# 3_-STM32F103_Debugger.net
KiCad netlist of a schematic drawn in Altium Designer
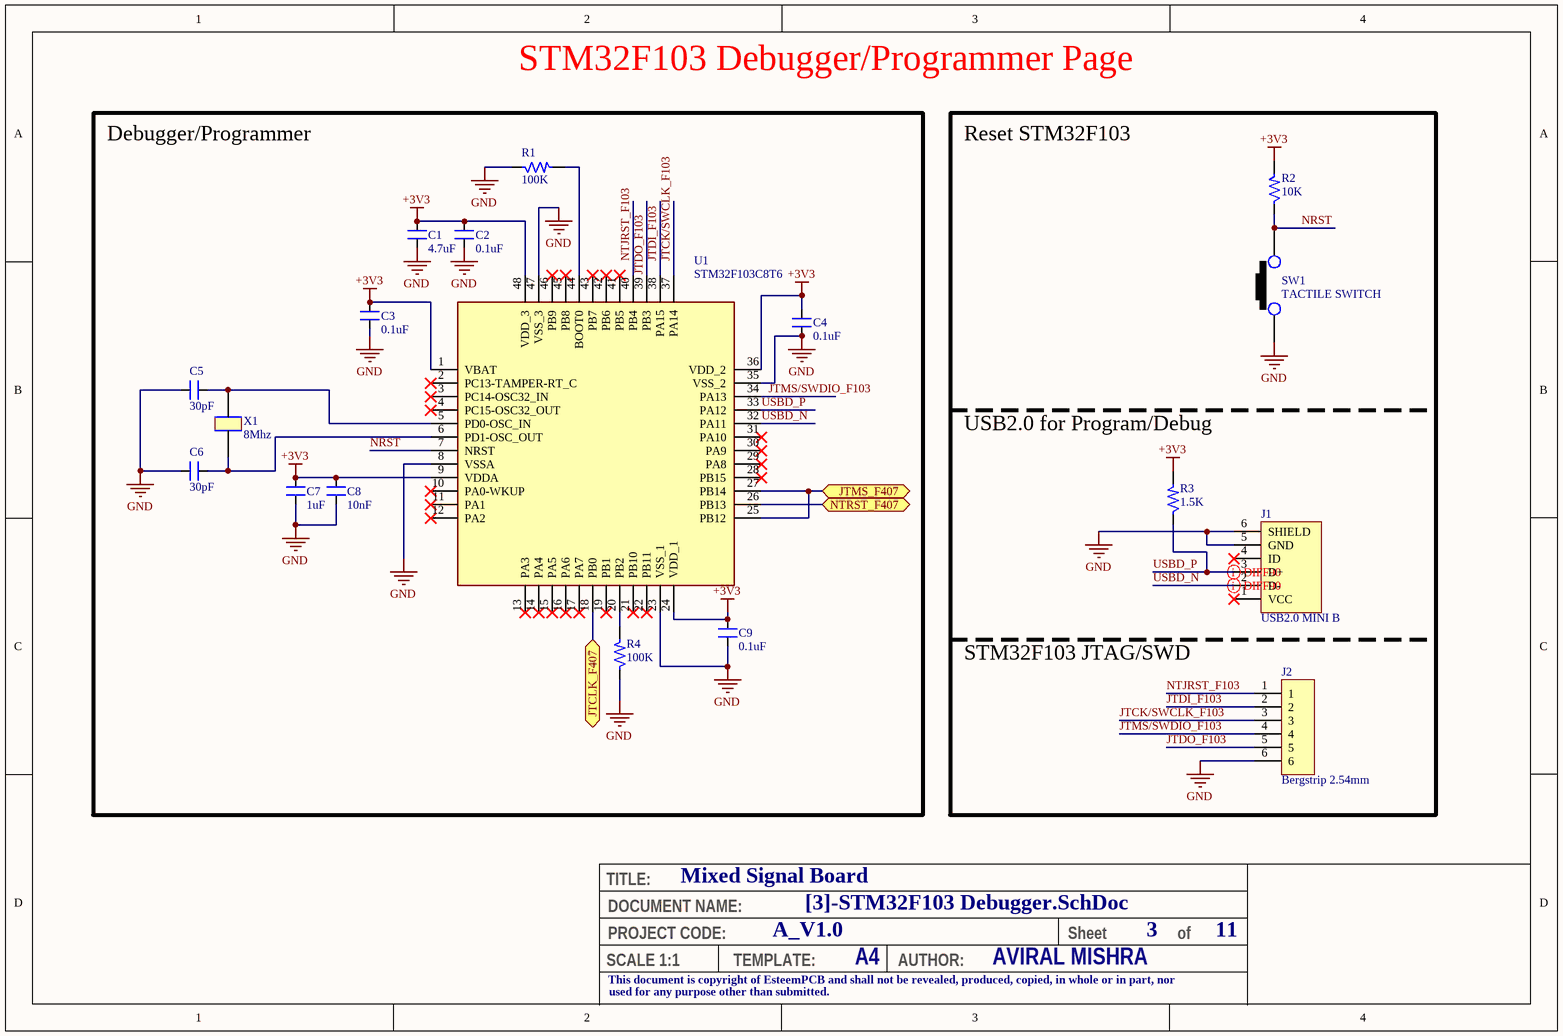
[diagram p0: [3]-STM32F103 Debugger.SchDoc]

(export (version "E")
  (design (tool "Eeschema 10.0.6"))
  (components
    (comp (ref "C1")
      (value "4.7uF")
      (footprint "CAP_0805")
      (description "4.7µF ±10% 50V Ceramic Capacitor X5R 0805 (2012 Metric)")
      (fields
        (field (name "MANUFACTURER") "Yageo")
        (field (name "MANUFACTURER PART NUMBER") "GRM21BR61H475KE51L")
      )
      (libsource (lib "ESTEEMPCBLIB") (part "CAP_4.7uF-50V-10%-0805"))
    )
    (comp (ref "C2")
      (value "0.1uF")
      (footprint "CAP_0805")
      (description "0.1µF ±10% 50V Ceramic Capacitor X7R 0805 (2012 Metric)")
      (fields
        (field (name "MANUFACTURER") "Samsung")
        (field (name "MANUFACTURER PART NUMBER") "CL21B104KBCNNNC")
      )
      (libsource (lib "ESTEEMPCBLIB") (part "CAP_0.1uF-50V-10%-0805"))
    )
    (comp (ref "C3")
      (value "0.1uF")
      (footprint "CAP_0805")
      (description "0.1µF ±10% 50V Ceramic Capacitor X7R 0805 (2012 Metric)")
      (fields
        (field (name "MANUFACTURER") "Samsung")
        (field (name "MANUFACTURER PART NUMBER") "CL21B104KBCNNNC")
      )
      (libsource (lib "ESTEEMPCBLIB") (part "CAP_0.1uF-50V-10%-0805"))
    )
    (comp (ref "C4")
      (value "0.1uF")
      (footprint "CAP_0805")
      (description "0.1µF ±10% 50V Ceramic Capacitor X7R 0805 (2012 Metric)")
      (fields
        (field (name "MANUFACTURER") "Samsung")
        (field (name "MANUFACTURER PART NUMBER") "CL21B104KBCNNNC")
      )
      (libsource (lib "ESTEEMPCBLIB") (part "CAP_0.1uF-50V-10%-0805"))
    )
    (comp (ref "C5")
      (value "30pF")
      (footprint "CAP_0805")
      (description "±10% 50V Ceramic Capacitor C0G, NP0 0805 (2012 Metric)")
      (fields
        (field (name "MANUFACTURER PART NUMBER") "C0805C300K5GAC7800")
        (field (name "MANUFACTURER") "KEMET")
      )
      (libsource (lib "ESTEEMPCBLIB") (part "CAP_30pF-50V-10%-0805"))
    )
    (comp (ref "C6")
      (value "30pF")
      (footprint "CAP_0805")
      (description "±10% 50V Ceramic Capacitor C0G, NP0 0805 (2012 Metric)")
      (fields
        (field (name "MANUFACTURER PART NUMBER") "C0805C300K5GAC7800")
        (field (name "MANUFACTURER") "KEMET")
      )
      (libsource (lib "ESTEEMPCBLIB") (part "CAP_30pF-50V-10%-0805"))
    )
    (comp (ref "C7")
      (value "1uF")
      (footprint "CAP_0805")
      (description "1µF ±5% 50V Ceramic Capacitor X7R 0805 (2012 Metric)")
      (fields
        (field (name "MANUFACTURER") "Samsung")
        (field (name "MANUFACTURER PART NUMBER") "CC0805JKX7R9BB105")
      )
      (libsource (lib "ESTEEMPCBLIB") (part "CAP_1uF-50V-5%-0805"))
    )
    (comp (ref "C8")
      (value "10nF")
      (footprint "CAP_0805")
      (description "10000pF ±10% 50V Ceramic Capacitor X7R 0805 (2012 Metric)")
      (fields
        (field (name "MANUFACTURER") "Samsung")
        (field (name "MANUFACTURER PART NUMBER") "C0805C103K5RECAUTO")
      )
      (libsource (lib "ESTEEMPCBLIB") (part "CAP_10nF-50V-10%-0805"))
    )
    (comp (ref "C9")
      (value "0.1uF")
      (footprint "CAP_0805")
      (description "0.1µF ±10% 50V Ceramic Capacitor X7R 0805 (2012 Metric)")
      (fields
        (field (name "MANUFACTURER") "Samsung")
        (field (name "MANUFACTURER PART NUMBER") "CL21B104KBCNNNC")
      )
      (libsource (lib "ESTEEMPCBLIB") (part "CAP_0.1uF-50V-10%-0805"))
    )
    (comp (ref "J1")
      (value "USB2.0 MINI B")
      (footprint "CON_690-005-299-043")
      (description "USB - mini B USB 2.0 Receptacle Connector 5 Position Surface Mount, Right Angle")
      (fields
        (field (name "MANUFACTURER") "EDAC")
        (field (name "MANUFACTURER PART NUMBER") "690-005-299-043")
      )
      (libsource (lib "ESTEEMPCBLIB") (part "CON_USB2.0-MINIB-SMD"))
    )
    (comp (ref "J2")
      (value "Bergstrip 2.54mm")
      (footprint "CON6_100_59D78_TH_ST")
      (description "6 Pins, 1 Row 2.54mm Pitch, Straight bergstrip, Female")
      (fields (field (name "MANUFACTURER") "Molex") (field (name "MANUFACTURER PART NUMBER") "22-10-2061"))
      (libsource (lib "ESTEEMPCBLIB") (part "CON-BS-SKT_6X1-100-ST-TH"))
    )
    (comp (ref "R1")
      (value "100K")
      (footprint "RES_0603")
      (description "100 kOhms ±1% 0.1W, 1/10W Chip Resistor 0603 (1608 Metric) Automotive AEC-Q200 Thick Film")
      (fields
        (field (name "MANUFACTURER") "Stackpole Electronics")
        (field (name "MANUFACTURER PART NUMBER") "RMCF0603FT100K")
      )
      (libsource (lib "ESTEEMPCBLIB") (part "RES_100K-0.1W-1%-0603"))
    )
    (comp (ref "R2")
      (value "10K")
      (footprint "RES_0603")
      (description "10 kOhms ±1% 0.1W, 1/10W Chip Resistor 0603 (1608 Metric) Automotive AEC-Q200 Thick Film")
      (fields (field (name "MANUFACTURER") "Walsin") (field (name "MANUFACTURER PART NUMBER") "WR06X1002FTL"))
      (libsource (lib "ESTEEMPCBLIB") (part "RES_10K-0.1W-1%-0603"))
    )
    (comp (ref "R3")
      (value "1.5K")
      (footprint "RES_0805")
      (description "1.5 kOhms ±1% 0.125W, 1/8W Chip Resistor 0805 (2012 Metric) Thick Film")
      (fields
        (field (name "MANUFACTURER") "TE Connectivity Passive Product")
        (field (name "MANUFACTURER PART NUMBER") "CRG0805F1K5")
      )
      (libsource (lib "ESTEEMPCBLIB") (part "RES_1.5K-0.125W-1%-0805"))
    )
    (comp (ref "R4")
      (value "100K")
      (footprint "RES_0603")
      (description "100 kOhms ±1% 0.1W, 1/10W Chip Resistor 0603 (1608 Metric) Automotive AEC-Q200 Thick Film")
      (fields
        (field (name "MANUFACTURER") "Stackpole Electronics")
        (field (name "MANUFACTURER PART NUMBER") "RMCF0603FT100K")
      )
      (libsource (lib "ESTEEMPCBLIB") (part "RES_100K-0.1W-1%-0603"))
    )
    (comp (ref "SW1")
      (value "TACTILE SWITCH")
      (footprint "SW_342_SMD")
      (description "Tactile Switch SPST-NO Top Actuated Surface Mount")
      (fields
        (field (name "MANUFACTURER") "ITT C&K")
        (field (name "MANUFACTURER PART NUMBER") "RS-282G05A3-SMRT")
      )
      (libsource (lib "ESTEEMPCBLIB") (part "SW1_RS-282G05A3-SMRT-SMD"))
    )
    (comp (ref "U1")
      (value "STM32F103C8T6")
      (footprint "LQFP-48_19.6_393_58X11_SMD")
      (description "ARM® Cortex®-M3 STM32F1 Microcontroller IC 32-Bit 72MHz 64KB (64K x 8) FLASH 48-LQFP (7x7)")
      (fields (field (name "MANUFACTURER") "STMicroelectronics"))
      (libsource (lib "ESTEEMPCBLIB") (part "IC_STM32F103C8T6"))
    )
    (comp (ref "X1")
      (value "8Mhz")
      (footprint "XTAL_314_240X47_SMD")
      (description "8MHz ±30ppm Crystal 32pF 60 Ohms HC-49/US")
      (fields
        (field (name "MANUFACTURER") "Fox Electronics")
        (field (name "MANUFACTURER PART NUMBER") "ECS-80-32-5PX-TR")
      )
      (libsource (lib "ESTEEMPCBLIB") (part "XTAL_8MHZ-ECS-80-32-5PX-SMD"))
    )
  )
  (nets
    (net (code "1") (name "+3V3") (class "Default")
      (node (ref "C1") (pin "2") (pinfunction "2_2") (pintype "passive"))
      (node (ref "C2") (pin "2") (pinfunction "2_2") (pintype "passive"))
      (node (ref "C3") (pin "2") (pinfunction "2_2") (pintype "passive"))
      (node (ref "C4") (pin "2") (pinfunction "2_2") (pintype "passive"))
      (node (ref "C7") (pin "2") (pinfunction "2_2") (pintype "passive"))
      (node (ref "C8") (pin "2") (pinfunction "2_2") (pintype "passive"))
      (node (ref "C9") (pin "2") (pinfunction "2_2") (pintype "passive"))
      (node (ref "R2") (pin "2") (pinfunction "2_2") (pintype "passive"))
      (node (ref "R3") (pin "2") (pinfunction "2_2") (pintype "passive"))
      (node (ref "U1") (pin "1") (pinfunction "VBAT_1") (pintype "passive"))
      (node (ref "U1") (pin "24") (pinfunction "VDD_1_24") (pintype "passive"))
      (node (ref "U1") (pin "36") (pinfunction "VDD_2_36") (pintype "passive"))
      (node (ref "U1") (pin "48") (pinfunction "VDD_3_48") (pintype "passive"))
      (node (ref "U1") (pin "9") (pinfunction "VDDA_9") (pintype "passive"))
    )
    (net (code "2") (name "/JTCK{slash}SWCLK_F103") (class "Default")
      (node (ref "J2") (pin "3") (pinfunction "3_3") (pintype "passive"))
      (node (ref "U1") (pin "37") (pinfunction "PA14_37") (pintype "passive"))
    )
    (net (code "3") (name "/JTCLK_F407") (class "Default")
      (node (ref "U1") (pin "18") (pinfunction "PB0_18") (pintype "passive"))
    )
    (net (code "4") (name "/JTDI_F103") (class "Default")
      (node (ref "J2") (pin "2") (pinfunction "2_2") (pintype "passive"))
      (node (ref "U1") (pin "38") (pinfunction "PA15_38") (pintype "passive"))
    )
    (net (code "5") (name "/JTDO_F103") (class "Default")
      (node (ref "J2") (pin "5") (pinfunction "5_5") (pintype "passive"))
      (node (ref "U1") (pin "39") (pinfunction "PB3_39") (pintype "passive"))
    )
    (net (code "6") (name "/JTMS_F407") (class "Default")
      (node (ref "U1") (pin "25") (pinfunction "PB12_25") (pintype "passive"))
      (node (ref "U1") (pin "27") (pinfunction "PB14_27") (pintype "passive"))
    )
    (net (code "7") (name "/JTMS{slash}SWDIO_F103") (class "Default")
      (node (ref "J2") (pin "4") (pinfunction "4_4") (pintype "passive"))
      (node (ref "U1") (pin "34") (pinfunction "PA13_34") (pintype "passive"))
    )
    (net (code "8") (name "/NRST") (class "Default")
      (node (ref "R2") (pin "1") (pinfunction "1_1") (pintype "passive"))
      (node (ref "SW1") (pin "2") (pinfunction "2_2") (pintype "passive"))
      (node (ref "U1") (pin "7") (pinfunction "NRST_7") (pintype "passive"))
    )
    (net (code "9") (name "/NTJRST_F103") (class "Default")
      (node (ref "J2") (pin "1") (pinfunction "1_1") (pintype "passive"))
      (node (ref "U1") (pin "40") (pinfunction "PB4_40") (pintype "passive"))
    )
    (net (code "10") (name "/NTRST_F407") (class "Default")
      (node (ref "U1") (pin "26") (pinfunction "PB13_26") (pintype "passive"))
    )
    (net (code "11") (name "/USBD_N") (class "Default")
      (node (ref "J1") (pin "2") (pinfunction "D-_2") (pintype "passive"))
      (node (ref "U1") (pin "32") (pinfunction "PA11_32") (pintype "passive"))
    )
    (net (code "12") (name "/USBD_P") (class "Default")
      (node (ref "J1") (pin "3") (pinfunction "D+_3") (pintype "passive"))
      (node (ref "R3") (pin "1") (pinfunction "1_1") (pintype "passive"))
      (node (ref "U1") (pin "33") (pinfunction "PA12_33") (pintype "passive"))
    )
    (net (code "13") (name "GND") (class "Default")
      (node (ref "C1") (pin "1") (pinfunction "1_1") (pintype "passive"))
      (node (ref "C2") (pin "1") (pinfunction "1_1") (pintype "passive"))
      (node (ref "C3") (pin "1") (pinfunction "1_1") (pintype "passive"))
      (node (ref "C4") (pin "1") (pinfunction "1_1") (pintype "passive"))
      (node (ref "C5") (pin "1") (pinfunction "1_1") (pintype "passive"))
      (node (ref "C6") (pin "1") (pinfunction "1_1") (pintype "passive"))
      (node (ref "C7") (pin "1") (pinfunction "1_1") (pintype "passive"))
      (node (ref "C8") (pin "1") (pinfunction "1_1") (pintype "passive"))
      (node (ref "C9") (pin "1") (pinfunction "1_1") (pintype "passive"))
      (node (ref "J1") (pin "5") (pinfunction "GND_5") (pintype "passive"))
      (node (ref "J1") (pin "6") (pinfunction "SHIELD_6") (pintype "passive"))
      (node (ref "J2") (pin "6") (pinfunction "6_6") (pintype "passive"))
      (node (ref "R1") (pin "1") (pinfunction "1_1") (pintype "passive"))
      (node (ref "R4") (pin "1") (pinfunction "1_1") (pintype "passive"))
      (node (ref "SW1") (pin "1") (pinfunction "1_1") (pintype "passive"))
      (node (ref "U1") (pin "23") (pinfunction "VSS_1_23") (pintype "passive"))
      (node (ref "U1") (pin "35") (pinfunction "VSS_2_35") (pintype "passive"))
      (node (ref "U1") (pin "47") (pinfunction "VSS_3_47") (pintype "passive"))
      (node (ref "U1") (pin "8") (pinfunction "VSSA_8") (pintype "passive"))
    )
    (net (code "14") (name "Net-(U1-BOOT0)") (class "Default")
      (node (ref "R1") (pin "2") (pinfunction "2_2") (pintype "passive"))
      (node (ref "U1") (pin "44") (pinfunction "BOOT0_44") (pintype "passive"))
    )
    (net (code "15") (name "Net-(U1-PB2)") (class "Default")
      (node (ref "R4") (pin "2") (pinfunction "2_2") (pintype "passive"))
      (node (ref "U1") (pin "20") (pinfunction "PB2_20") (pintype "passive"))
    )
    (net (code "16") (name "Net-(U1-PD0-OSC_IN)") (class "Default")
      (node (ref "C5") (pin "2") (pinfunction "2_2") (pintype "passive"))
      (node (ref "U1") (pin "5") (pinfunction "PD0-OSC_IN_5") (pintype "passive"))
      (node (ref "X1") (pin "2") (pinfunction "2_2") (pintype "passive"))
    )
    (net (code "17") (name "Net-(U1-PD1-OSC_OUT)") (class "Default")
      (node (ref "C6") (pin "2") (pinfunction "2_2") (pintype "passive"))
      (node (ref "U1") (pin "6") (pinfunction "PD1-OSC_OUT_6") (pintype "passive"))
      (node (ref "X1") (pin "1") (pinfunction "1_1") (pintype "passive"))
    )
    (net (code "18") (name "unconnected-(J1-ID-Pad4)") (class "Default")
      (node (ref "J1") (pin "4") (pinfunction "ID_4") (pintype "passive+no_connect"))
    )
    (net (code "19") (name "unconnected-(J1-VCC-Pad1)") (class "Default")
      (node (ref "J1") (pin "1") (pinfunction "VCC_1") (pintype "passive+no_connect"))
    )
    (net (code "20") (name "unconnected-(U1-PA0-WKUP-Pad10)") (class "Default")
      (node (ref "U1") (pin "10") (pinfunction "PA0-WKUP_10") (pintype "passive+no_connect"))
    )
    (net (code "21") (name "unconnected-(U1-PA1-Pad11)") (class "Default")
      (node (ref "U1") (pin "11") (pinfunction "PA1_11") (pintype "passive+no_connect"))
    )
    (net (code "22") (name "unconnected-(U1-PA2-Pad12)") (class "Default")
      (node (ref "U1") (pin "12") (pinfunction "PA2_12") (pintype "passive+no_connect"))
    )
    (net (code "23") (name "unconnected-(U1-PA3-Pad13)") (class "Default")
      (node (ref "U1") (pin "13") (pinfunction "PA3_13") (pintype "passive+no_connect"))
    )
    (net (code "24") (name "unconnected-(U1-PA4-Pad14)") (class "Default")
      (node (ref "U1") (pin "14") (pinfunction "PA4_14") (pintype "passive+no_connect"))
    )
    (net (code "25") (name "unconnected-(U1-PA5-Pad15)") (class "Default")
      (node (ref "U1") (pin "15") (pinfunction "PA5_15") (pintype "passive+no_connect"))
    )
    (net (code "26") (name "unconnected-(U1-PA6-Pad16)") (class "Default")
      (node (ref "U1") (pin "16") (pinfunction "PA6_16") (pintype "passive+no_connect"))
    )
    (net (code "27") (name "unconnected-(U1-PA7-Pad17)") (class "Default")
      (node (ref "U1") (pin "17") (pinfunction "PA7_17") (pintype "passive+no_connect"))
    )
    (net (code "28") (name "unconnected-(U1-PA8-Pad29)") (class "Default")
      (node (ref "U1") (pin "29") (pinfunction "PA8_29") (pintype "passive+no_connect"))
    )
    (net (code "29") (name "unconnected-(U1-PA9-Pad30)") (class "Default")
      (node (ref "U1") (pin "30") (pinfunction "PA9_30") (pintype "passive+no_connect"))
    )
    (net (code "30") (name "unconnected-(U1-PA10-Pad31)") (class "Default")
      (node (ref "U1") (pin "31") (pinfunction "PA10_31") (pintype "passive+no_connect"))
    )
    (net (code "31") (name "unconnected-(U1-PB1-Pad19)") (class "Default")
      (node (ref "U1") (pin "19") (pinfunction "PB1_19") (pintype "passive+no_connect"))
    )
    (net (code "32") (name "unconnected-(U1-PB5-Pad41)") (class "Default")
      (node (ref "U1") (pin "41") (pinfunction "PB5_41") (pintype "passive+no_connect"))
    )
    (net (code "33") (name "unconnected-(U1-PB6-Pad42)") (class "Default")
      (node (ref "U1") (pin "42") (pinfunction "PB6_42") (pintype "passive+no_connect"))
    )
    (net (code "34") (name "unconnected-(U1-PB7-Pad43)") (class "Default")
      (node (ref "U1") (pin "43") (pinfunction "PB7_43") (pintype "passive+no_connect"))
    )
    (net (code "35") (name "unconnected-(U1-PB8-Pad45)") (class "Default")
      (node (ref "U1") (pin "45") (pinfunction "PB8_45") (pintype "passive+no_connect"))
    )
    (net (code "36") (name "unconnected-(U1-PB9-Pad46)") (class "Default")
      (node (ref "U1") (pin "46") (pinfunction "PB9_46") (pintype "passive+no_connect"))
    )
    (net (code "37") (name "unconnected-(U1-PB10-Pad21)") (class "Default")
      (node (ref "U1") (pin "21") (pinfunction "PB10_21") (pintype "passive+no_connect"))
    )
    (net (code "38") (name "unconnected-(U1-PB11-Pad22)") (class "Default")
      (node (ref "U1") (pin "22") (pinfunction "PB11_22") (pintype "passive+no_connect"))
    )
    (net (code "39") (name "unconnected-(U1-PB15-Pad28)") (class "Default")
      (node (ref "U1") (pin "28") (pinfunction "PB15_28") (pintype "passive+no_connect"))
    )
    (net (code "40") (name "unconnected-(U1-PC13-TAMPER-RT_C-Pad2)") (class "Default")
      (node (ref "U1") (pin "2") (pinfunction "PC13-TAMPER-RT_C_2") (pintype "passive+no_connect"))
    )
    (net (code "41") (name "unconnected-(U1-PC14-OSC32_IN-Pad3)") (class "Default")
      (node (ref "U1") (pin "3") (pinfunction "PC14-OSC32_IN_3") (pintype "passive+no_connect"))
    )
    (net (code "42") (name "unconnected-(U1-PC15-OSC32_OUT-Pad4)") (class "Default")
      (node (ref "U1") (pin "4") (pinfunction "PC15-OSC32_OUT_4") (pintype "passive+no_connect"))
    )
  )
)
